# Puncher.net
KiCad netlist of a schematic drawn in EAGLE
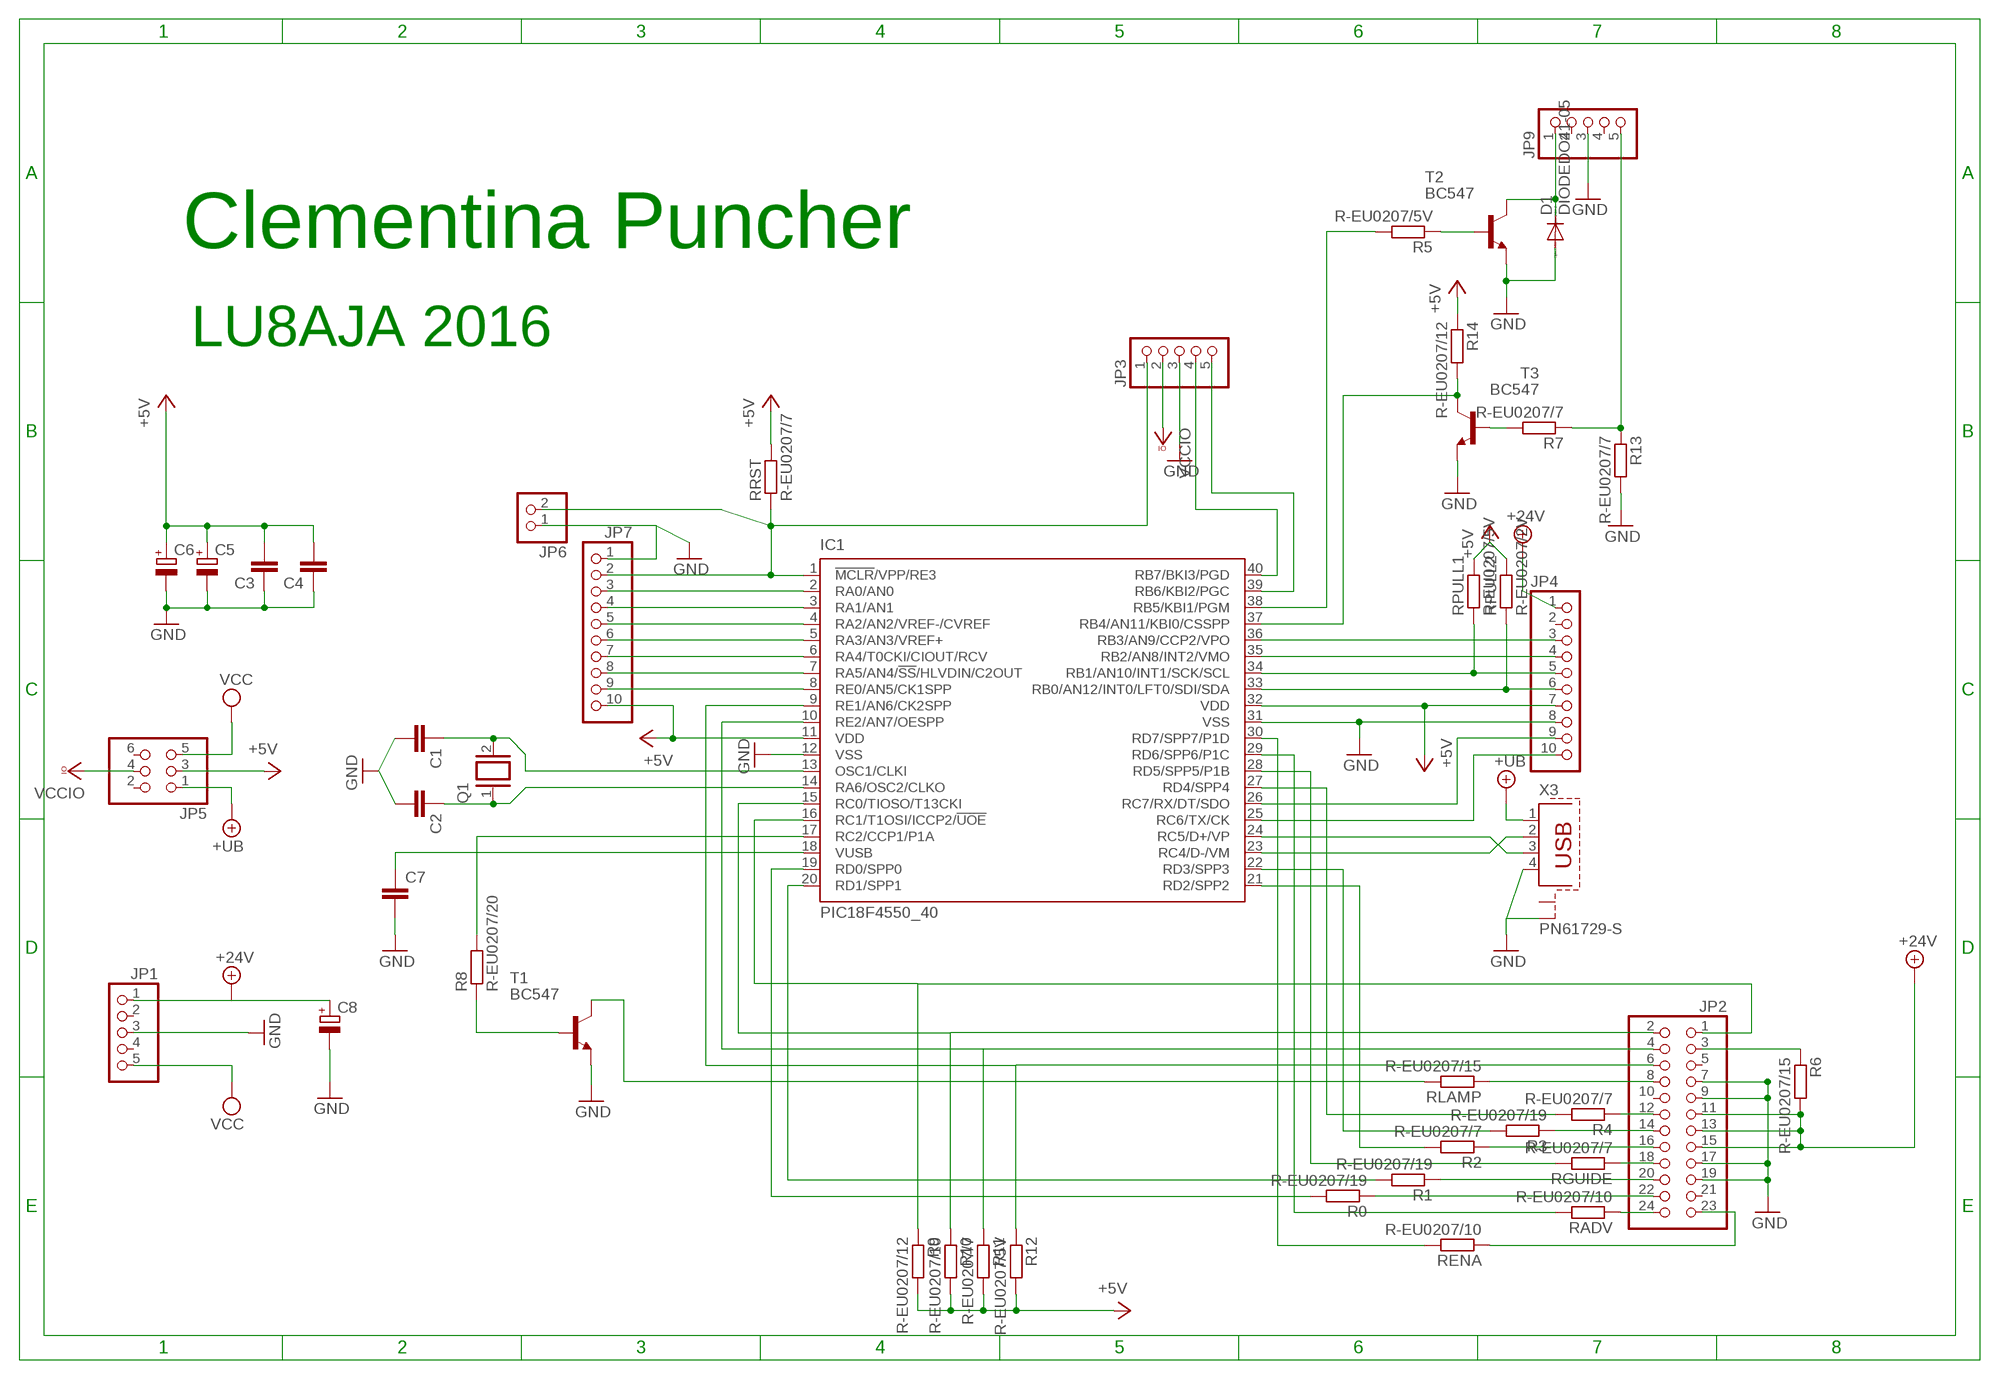
[diagram p0: schematic, sheet 1]

(export (version "E")
  (design (tool "Eeschema 10.0.6"))
  (components
    (comp (ref "C1")
      (value "C-EU025-025X050")
      (footprint "eagle-import:C025-025X050")
      (libsource (lib "eagle-import") (part "rcl_C-EU025-025X050"))
    )
    (comp (ref "C2")
      (value "C-EU025-025X050")
      (footprint "eagle-import:C025-025X050")
      (libsource (lib "eagle-import") (part "rcl_C-EU025-025X050"))
    )
    (comp (ref "C3")
      (value "C-EU050-025X075")
      (footprint "eagle-import:C050-025X075")
      (libsource (lib "eagle-import") (part "rcl_C-EU050-025X075"))
    )
    (comp (ref "C4")
      (value "C-EU025-030X050")
      (footprint "eagle-import:C025-030X050")
      (libsource (lib "eagle-import") (part "C-EU025-030X050"))
    )
    (comp (ref "C5")
      (value "CPOL-EUE5-8.5")
      (footprint "eagle-import:E5-8,5")
      (libsource (lib "eagle-import") (part "rcl_CPOL-EUE5-8.5"))
    )
    (comp (ref "C6")
      (value "CPOL-EUE5-8.5")
      (footprint "eagle-import:E5-8,5")
      (libsource (lib "eagle-import") (part "rcl_CPOL-EUE5-8.5"))
    )
    (comp (ref "C7")
      (value "C-EU050-025X075")
      (footprint "eagle-import:C050-025X075")
      (libsource (lib "eagle-import") (part "C-EU050-025X075"))
    )
    (comp (ref "C8")
      (value "CPOL-EUE5-8.5")
      (footprint "eagle-import:E5-8,5")
      (libsource (lib "eagle-import") (part "CPOL-EUE5-8.5"))
    )
    (comp (ref "D1")
      (value "DIODEDO41-05")
      (footprint "eagle-import:DO41-05")
      (libsource (lib "eagle-import") (part "DIODEDO41-05"))
    )
    (comp (ref "IC1")
      (value "PIC18F4550_40")
      (footprint "eagle-import:DIL40")
      (fields (field (name "MF") "MICROCHIP") (field (name "MPN") "PIC18F4550-I/P"))
      (libsource (lib "eagle-import") (part "PIC18F4_40550"))
    )
    (comp (ref "JP1")
      (value "PINHD-1X5")
      (footprint "eagle-import:1X05")
      (libsource (lib "eagle-import") (part "PINHD-1X5"))
    )
    (comp (ref "JP2")
      (value "PINHD-2X12")
      (footprint "eagle-import:2X12")
      (libsource (lib "eagle-import") (part "PINHD-2X12"))
    )
    (comp (ref "JP3")
      (value "PINHD-1X5")
      (footprint "eagle-import:1X05")
      (libsource (lib "eagle-import") (part "PINHD-1X5"))
    )
    (comp (ref "JP4")
      (value "PINHD-1X10")
      (footprint "eagle-import:1X10")
      (libsource (lib "eagle-import") (part "PINHD-1X10"))
    )
    (comp (ref "JP5")
      (value "PINHD-2X3")
      (footprint "eagle-import:2X03")
      (libsource (lib "eagle-import") (part "PINHD-2X3"))
    )
    (comp (ref "JP6")
      (value "PINHD-1X2")
      (footprint "eagle-import:1X02")
      (libsource (lib "eagle-import") (part "PINHD-1X2"))
    )
    (comp (ref "JP7")
      (value "PINHD-1X10")
      (footprint "eagle-import:1X10")
      (libsource (lib "eagle-import") (part "PINHD-1X10"))
    )
    (comp (ref "JP9")
      (value "PINHD-1X5")
      (footprint "eagle-import:1X05")
      (libsource (lib "eagle-import") (part "PINHD-1X5"))
    )
    (comp (ref "Q1")
      (value "XTAL/S")
      (footprint "eagle-import:QS")
      (libsource (lib "eagle-import") (part "XTAL/S"))
    )
    (comp (ref "R0")
      (value "R-EU0207/19")
      (footprint "eagle-import:0207_19")
      (libsource (lib "eagle-import") (part "R-EU0207/19"))
    )
    (comp (ref "R1")
      (value "R-EU0207/19")
      (footprint "eagle-import:0207_19")
      (libsource (lib "eagle-import") (part "R-EU0207/19"))
    )
    (comp (ref "R2")
      (value "R-EU0207/7")
      (footprint "eagle-import:0207_7")
      (libsource (lib "eagle-import") (part "R-EU0207/7"))
    )
    (comp (ref "R3")
      (value "R-EU0207/19")
      (footprint "eagle-import:0207_19")
      (libsource (lib "eagle-import") (part "R-EU0207/19"))
    )
    (comp (ref "R4")
      (value "R-EU0207/7")
      (footprint "eagle-import:0207_7")
      (libsource (lib "eagle-import") (part "R-EU0207/7"))
    )
    (comp (ref "R5")
      (value "R-EU0207/5V")
      (footprint "eagle-import:0207_5V")
      (libsource (lib "eagle-import") (part "R-EU0207/5V"))
    )
    (comp (ref "R6")
      (value "R-EU0207/15")
      (footprint "eagle-import:0207_15")
      (libsource (lib "eagle-import") (part "R-EU0207/15"))
    )
    (comp (ref "R7")
      (value "R-EU0207/7")
      (footprint "eagle-import:0207_7")
      (libsource (lib "eagle-import") (part "R-EU0207/7"))
    )
    (comp (ref "R8")
      (value "R-EU0207/20")
      (footprint "eagle-import:0207_20")
      (libsource (lib "eagle-import") (part "R-EU0207/20"))
    )
    (comp (ref "R9")
      (value "R-EU0207/12")
      (footprint "eagle-import:0207_12")
      (libsource (lib "eagle-import") (part "R-EU0207/12"))
    )
    (comp (ref "R10")
      (value "R-EU0207/10")
      (footprint "eagle-import:0207_10")
      (libsource (lib "eagle-import") (part "R-EU0207/10"))
    )
    (comp (ref "R11")
      (value "R-EU0207/7")
      (footprint "eagle-import:0207_7")
      (libsource (lib "eagle-import") (part "R-EU0207/7"))
    )
    (comp (ref "R12")
      (value "R-EU0207/5V")
      (footprint "eagle-import:0207_5V")
      (libsource (lib "eagle-import") (part "R-EU0207/5V"))
    )
    (comp (ref "R13")
      (value "R-EU0207/7")
      (footprint "eagle-import:0207_7")
      (libsource (lib "eagle-import") (part "R-EU0207/7"))
    )
    (comp (ref "R14")
      (value "R-EU0207/12")
      (footprint "eagle-import:0207_12")
      (libsource (lib "eagle-import") (part "R-EU0207/12"))
    )
    (comp (ref "RADV")
      (value "R-EU0207/10")
      (footprint "eagle-import:0207_10")
      (libsource (lib "eagle-import") (part "R-EU0207/10"))
    )
    (comp (ref "RENA")
      (value "R-EU0207/10")
      (footprint "eagle-import:0207_10")
      (libsource (lib "eagle-import") (part "R-EU0207/10"))
    )
    (comp (ref "RGUIDE")
      (value "R-EU0207/7")
      (footprint "eagle-import:0207_7")
      (libsource (lib "eagle-import") (part "R-EU0207/7"))
    )
    (comp (ref "RLAMP")
      (value "R-EU0207/15")
      (footprint "eagle-import:0207_15")
      (libsource (lib "eagle-import") (part "R-EU0207/15"))
    )
    (comp (ref "RPULL1")
      (value "R-EU0207/5V")
      (footprint "eagle-import:0207_5V")
      (libsource (lib "eagle-import") (part "R-EU0207/5V"))
    )
    (comp (ref "RPULL2")
      (value "R-EU0207/2V")
      (footprint "eagle-import:0207_2V")
      (libsource (lib "eagle-import") (part "R-EU0207/2V"))
    )
    (comp (ref "RRST")
      (value "R-EU0207/7")
      (footprint "eagle-import:0207_7")
      (libsource (lib "eagle-import") (part "R-EU0207/7"))
    )
    (comp (ref "T1")
      (value "BC547")
      (footprint "eagle-import:TO92")
      (libsource (lib "eagle-import") (part "BC547"))
    )
    (comp (ref "T2")
      (value "BC547")
      (footprint "eagle-import:TO92")
      (libsource (lib "eagle-import") (part "BC547"))
    )
    (comp (ref "T3")
      (value "BC547")
      (footprint "eagle-import:TO92")
      (libsource (lib "eagle-import") (part "BC547"))
    )
    (comp (ref "X3")
      (value "PN61729-S")
      (footprint "eagle-import:PN61729-S")
      (libsource (lib "eagle-import") (part "PN61729-S"))
    )
  )
  (nets
    (net (code "1") (name "+5V") (class "Default")
      (node (ref "C3") (pin "2") (pinfunction "2_2") (pintype "passive"))
      (node (ref "C4") (pin "2") (pinfunction "2_2") (pintype "passive"))
      (node (ref "C5") (pin "+") (pinfunction "+_+") (pintype "passive"))
      (node (ref "C6") (pin "+") (pinfunction "+_+") (pintype "passive"))
      (node (ref "IC1") (pin "11") (pinfunction "VDD_11") (pintype "power_in"))
      (node (ref "IC1") (pin "32") (pinfunction "VDD_32") (pintype "power_in"))
      (node (ref "JP4") (pin "7") (pinfunction "7_7") (pintype "passive"))
      (node (ref "JP5") (pin "3") (pinfunction "3_3") (pintype "passive"))
      (node (ref "JP7") (pin "10") (pinfunction "10_10") (pintype "passive"))
      (node (ref "R10") (pin "2") (pinfunction "2_2") (pintype "passive"))
      (node (ref "R11") (pin "2") (pinfunction "2_2") (pintype "passive"))
      (node (ref "R12") (pin "2") (pinfunction "2_2") (pintype "passive"))
      (node (ref "R14") (pin "1") (pinfunction "1_1") (pintype "passive"))
      (node (ref "R9") (pin "2") (pinfunction "2_2") (pintype "passive"))
      (node (ref "RPULL1") (pin "2") (pinfunction "2_2") (pintype "passive"))
      (node (ref "RPULL2") (pin "2") (pinfunction "2_2") (pintype "passive"))
      (node (ref "RRST") (pin "2") (pinfunction "2_2") (pintype "passive"))
    )
    (net (code "2") (name "+24V") (class "Default")
      (node (ref "C8") (pin "+") (pinfunction "+_+") (pintype "passive"))
      (node (ref "JP1") (pin "1") (pinfunction "1_1") (pintype "passive"))
      (node (ref "JP2") (pin "11") (pinfunction "11_11") (pintype "passive"))
      (node (ref "JP2") (pin "13") (pinfunction "13_13") (pintype "passive"))
      (node (ref "JP2") (pin "15") (pinfunction "15_15") (pintype "passive"))
      (node (ref "JP4") (pin "1") (pinfunction "1_1") (pintype "passive"))
      (node (ref "R6") (pin "2") (pinfunction "2_2") (pintype "passive"))
    )
    (net (code "3") (name "+UB") (class "Default")
      (node (ref "JP5") (pin "1") (pinfunction "1_1") (pintype "passive"))
      (node (ref "X3") (pin "1") (pinfunction "1_1") (pintype "passive"))
    )
    (net (code "4") (name "GND") (class "Default")
      (node (ref "C1") (pin "2") (pinfunction "2_2") (pintype "passive"))
      (node (ref "C2") (pin "2") (pinfunction "2_2") (pintype "passive"))
      (node (ref "C3") (pin "1") (pinfunction "1_1") (pintype "passive"))
      (node (ref "C4") (pin "1") (pinfunction "1_1") (pintype "passive"))
      (node (ref "C5") (pin "-") (pinfunction "-_-") (pintype "passive"))
      (node (ref "C6") (pin "-") (pinfunction "-_-") (pintype "passive"))
      (node (ref "C7") (pin "2") (pinfunction "2_2") (pintype "passive"))
      (node (ref "C8") (pin "-") (pinfunction "-_-") (pintype "passive"))
      (node (ref "D1") (pin "A") (pinfunction "A_A") (pintype "passive"))
      (node (ref "IC1") (pin "12") (pinfunction "VSS_12") (pintype "power_in"))
      (node (ref "IC1") (pin "31") (pinfunction "VSS_31") (pintype "power_in"))
      (node (ref "JP1") (pin "3") (pinfunction "3_3") (pintype "passive"))
      (node (ref "JP2") (pin "17") (pinfunction "17_17") (pintype "passive"))
      (node (ref "JP2") (pin "19") (pinfunction "19_19") (pintype "passive"))
      (node (ref "JP2") (pin "7") (pinfunction "7_7") (pintype "passive"))
      (node (ref "JP2") (pin "9") (pinfunction "9_9") (pintype "passive"))
      (node (ref "JP3") (pin "3") (pinfunction "3_3") (pintype "passive"))
      (node (ref "JP4") (pin "8") (pinfunction "8_8") (pintype "passive"))
      (node (ref "JP6") (pin "1") (pinfunction "1_1") (pintype "passive"))
      (node (ref "JP7") (pin "1") (pinfunction "1_1") (pintype "passive"))
      (node (ref "JP9") (pin "3") (pinfunction "3_3") (pintype "passive"))
      (node (ref "R13") (pin "2") (pinfunction "2_2") (pintype "passive"))
      (node (ref "T1") (pin "1") (pinfunction "E_1") (pintype "passive"))
      (node (ref "T2") (pin "1") (pinfunction "E_1") (pintype "passive"))
      (node (ref "T3") (pin "1") (pinfunction "E_1") (pintype "passive"))
      (node (ref "X3") (pin "4") (pinfunction "4_4") (pintype "passive"))
      (node (ref "X3") (pin "S2") (pinfunction "S2_S2") (pintype "passive"))
    )
    (net (code "5") (name "Net-(IC1-OSC1{slash}CLKI)") (class "Default")
      (node (ref "C1") (pin "1") (pinfunction "1_1") (pintype "passive"))
      (node (ref "IC1") (pin "13") (pinfunction "OSC1/CLKI_13") (pintype "input"))
      (node (ref "Q1") (pin "2") (pinfunction "2_2") (pintype "passive"))
    )
    (net (code "6") (name "Net-(IC1-RA0{slash}AN0)") (class "Default")
      (node (ref "IC1") (pin "2") (pinfunction "RA0/AN0_2") (pintype "bidirectional"))
      (node (ref "JP7") (pin "3") (pinfunction "3_3") (pintype "passive"))
    )
    (net (code "7") (name "Net-(IC1-RA1{slash}AN1)") (class "Default")
      (node (ref "IC1") (pin "3") (pinfunction "RA1/AN1_3") (pintype "bidirectional"))
      (node (ref "JP7") (pin "4") (pinfunction "4_4") (pintype "passive"))
    )
    (net (code "8") (name "Net-(IC1-RA2{slash}AN2{slash}VREF-{slash}CVREF)") (class "Default")
      (node (ref "IC1") (pin "4") (pinfunction "RA2/AN2/VREF-/CVREF_4") (pintype "bidirectional"))
      (node (ref "JP7") (pin "5") (pinfunction "5_5") (pintype "passive"))
    )
    (net (code "9") (name "Net-(IC1-RA3{slash}AN3{slash}VREF+)") (class "Default")
      (node (ref "IC1") (pin "5") (pinfunction "RA3/AN3/VREF+_5") (pintype "bidirectional"))
      (node (ref "JP7") (pin "6") (pinfunction "6_6") (pintype "passive"))
    )
    (net (code "10") (name "Net-(IC1-RA4{slash}T0CKI{slash}CIOUT{slash}RCV)") (class "Default")
      (node (ref "IC1") (pin "6") (pinfunction "RA4/T0CKI/CIOUT/RCV_6") (pintype "bidirectional"))
      (node (ref "JP7") (pin "7") (pinfunction "7_7") (pintype "passive"))
    )
    (net (code "11") (name "Net-(IC1-RA5{slash}AN4{slash}~{SS}{slash}HLVDIN{slash}C2OUT)") (class "Default")
      (node (ref "IC1") (pin "7") (pinfunction "RA5/AN4/~{SS}/HLVDIN/C2OUT_7") (pintype "bidirectional"))
      (node (ref "JP7") (pin "8") (pinfunction "8_8") (pintype "passive"))
    )
    (net (code "12") (name "Net-(IC1-RA6{slash}OSC2{slash}CLKO)") (class "Default")
      (node (ref "C2") (pin "1") (pinfunction "1_1") (pintype "passive"))
      (node (ref "IC1") (pin "14") (pinfunction "RA6/OSC2/CLKO_14") (pintype "output"))
      (node (ref "Q1") (pin "1") (pinfunction "1_1") (pintype "passive"))
    )
    (net (code "13") (name "Net-(IC1-RB0{slash}AN12{slash}INT0{slash}LFT0{slash}SDI{slash}SDA)") (class "Default")
      (node (ref "IC1") (pin "33") (pinfunction "RB0/AN12/INT0/LFT0/SDI/SDA_33") (pintype "bidirectional"))
      (node (ref "JP4") (pin "6") (pinfunction "6_6") (pintype "passive"))
      (node (ref "RPULL2") (pin "1") (pinfunction "1_1") (pintype "passive"))
    )
    (net (code "14") (name "Net-(IC1-RB1{slash}AN10{slash}INT1{slash}SCK{slash}SCL)") (class "Default")
      (node (ref "IC1") (pin "34") (pinfunction "RB1/AN10/INT1/SCK/SCL_34") (pintype "bidirectional"))
      (node (ref "JP4") (pin "5") (pinfunction "5_5") (pintype "passive"))
      (node (ref "RPULL1") (pin "1") (pinfunction "1_1") (pintype "passive"))
    )
    (net (code "15") (name "Net-(IC1-RB2{slash}AN8{slash}INT2{slash}VMO)") (class "Default")
      (node (ref "IC1") (pin "35") (pinfunction "RB2/AN8/INT2/VMO_35") (pintype "bidirectional"))
      (node (ref "JP4") (pin "4") (pinfunction "4_4") (pintype "passive"))
    )
    (net (code "16") (name "Net-(IC1-RB3{slash}AN9{slash}CCP2{slash}VPO)") (class "Default")
      (node (ref "IC1") (pin "36") (pinfunction "RB3/AN9/CCP2/VPO_36") (pintype "bidirectional"))
      (node (ref "JP4") (pin "3") (pinfunction "3_3") (pintype "passive"))
    )
    (net (code "17") (name "Net-(IC1-RB4{slash}AN11{slash}KBI0{slash}CSSPP)") (class "Default")
      (node (ref "IC1") (pin "37") (pinfunction "RB4/AN11/KBI0/CSSPP_37") (pintype "bidirectional"))
      (node (ref "R14") (pin "2") (pinfunction "2_2") (pintype "passive"))
      (node (ref "T3") (pin "3") (pinfunction "C_3") (pintype "passive"))
    )
    (net (code "18") (name "Net-(IC1-RB5{slash}KBI1{slash}PGM)") (class "Default")
      (node (ref "IC1") (pin "38") (pinfunction "RB5/KBI1/PGM_38") (pintype "bidirectional"))
      (node (ref "R5") (pin "2") (pinfunction "2_2") (pintype "passive"))
    )
    (net (code "19") (name "Net-(IC1-RB6{slash}KBI2{slash}PGC)") (class "Default")
      (node (ref "IC1") (pin "39") (pinfunction "RB6/KBI2/PGC_39") (pintype "bidirectional"))
      (node (ref "JP3") (pin "5") (pinfunction "5_5") (pintype "passive"))
    )
    (net (code "20") (name "Net-(IC1-RB7{slash}BKI3{slash}PGD)") (class "Default")
      (node (ref "IC1") (pin "40") (pinfunction "RB7/BKI3/PGD_40") (pintype "bidirectional"))
      (node (ref "JP3") (pin "4") (pinfunction "4_4") (pintype "passive"))
    )
    (net (code "21") (name "Net-(IC1-RC0{slash}TIOSO{slash}T13CKI)") (class "Default")
      (node (ref "IC1") (pin "15") (pinfunction "RC0/TIOSO/T13CKI_15") (pintype "bidirectional"))
      (node (ref "JP2") (pin "2") (pinfunction "2_2") (pintype "passive"))
      (node (ref "R10") (pin "1") (pinfunction "1_1") (pintype "passive"))
    )
    (net (code "22") (name "Net-(IC1-RC1{slash}T1OSI{slash}ICCP2{slash}~{UOE})") (class "Default")
      (node (ref "IC1") (pin "16") (pinfunction "RC1/T1OSI/ICCP2/~{UOE}_16") (pintype "bidirectional"))
      (node (ref "JP2") (pin "1") (pinfunction "1_1") (pintype "passive"))
      (node (ref "R9") (pin "1") (pinfunction "1_1") (pintype "passive"))
    )
    (net (code "23") (name "Net-(IC1-RC2{slash}CCP1{slash}P1A)") (class "Default")
      (node (ref "IC1") (pin "17") (pinfunction "RC2/CCP1/P1A_17") (pintype "bidirectional"))
      (node (ref "R8") (pin "2") (pinfunction "2_2") (pintype "passive"))
    )
    (net (code "24") (name "Net-(IC1-RC4{slash}D-{slash}VM)") (class "Default")
      (node (ref "IC1") (pin "23") (pinfunction "RC4/D-/VM_23") (pintype "bidirectional"))
      (node (ref "X3") (pin "2") (pinfunction "2_2") (pintype "passive"))
    )
    (net (code "25") (name "Net-(IC1-RC5{slash}D+{slash}VP)") (class "Default")
      (node (ref "IC1") (pin "24") (pinfunction "RC5/D+/VP_24") (pintype "bidirectional"))
      (node (ref "X3") (pin "3") (pinfunction "3_3") (pintype "passive"))
    )
    (net (code "26") (name "Net-(IC1-RC6{slash}TX{slash}CK)") (class "Default")
      (node (ref "IC1") (pin "25") (pinfunction "RC6/TX/CK_25") (pintype "bidirectional"))
      (node (ref "JP4") (pin "10") (pinfunction "10_10") (pintype "passive"))
    )
    (net (code "27") (name "Net-(IC1-RC7{slash}RX{slash}DT{slash}SDO)") (class "Default")
      (node (ref "IC1") (pin "26") (pinfunction "RC7/RX/DT/SDO_26") (pintype "bidirectional"))
      (node (ref "JP4") (pin "9") (pinfunction "9_9") (pintype "passive"))
    )
    (net (code "28") (name "Net-(IC1-RD0{slash}SPP0)") (class "Default")
      (node (ref "IC1") (pin "19") (pinfunction "RD0/SPP0_19") (pintype "bidirectional"))
      (node (ref "R0") (pin "2") (pinfunction "2_2") (pintype "passive"))
    )
    (net (code "29") (name "Net-(IC1-RD1{slash}SPP1)") (class "Default")
      (node (ref "IC1") (pin "20") (pinfunction "RD1/SPP1_20") (pintype "bidirectional"))
      (node (ref "R1") (pin "2") (pinfunction "2_2") (pintype "passive"))
    )
    (net (code "30") (name "Net-(IC1-RD2{slash}SPP2)") (class "Default")
      (node (ref "IC1") (pin "21") (pinfunction "RD2/SPP2_21") (pintype "bidirectional"))
      (node (ref "R2") (pin "2") (pinfunction "2_2") (pintype "passive"))
    )
    (net (code "31") (name "Net-(IC1-RD3{slash}SPP3)") (class "Default")
      (node (ref "IC1") (pin "22") (pinfunction "RD3/SPP3_22") (pintype "bidirectional"))
      (node (ref "R3") (pin "2") (pinfunction "2_2") (pintype "passive"))
    )
    (net (code "32") (name "Net-(IC1-RD4{slash}SPP4)") (class "Default")
      (node (ref "IC1") (pin "27") (pinfunction "RD4/SPP4_27") (pintype "bidirectional"))
      (node (ref "R4") (pin "2") (pinfunction "2_2") (pintype "passive"))
    )
    (net (code "33") (name "Net-(IC1-RD5{slash}SPP5{slash}P1B)") (class "Default")
      (node (ref "IC1") (pin "28") (pinfunction "RD5/SPP5/P1B_28") (pintype "bidirectional"))
      (node (ref "RGUIDE") (pin "2") (pinfunction "2_2") (pintype "passive"))
    )
    (net (code "34") (name "Net-(IC1-RD6{slash}SPP6{slash}P1C)") (class "Default")
      (node (ref "IC1") (pin "29") (pinfunction "RD6/SPP6/P1C_29") (pintype "bidirectional"))
      (node (ref "RADV") (pin "2") (pinfunction "2_2") (pintype "passive"))
    )
    (net (code "35") (name "Net-(IC1-RD7{slash}SPP7{slash}P1D)") (class "Default")
      (node (ref "IC1") (pin "30") (pinfunction "RD7/SPP7/P1D_30") (pintype "bidirectional"))
      (node (ref "RENA") (pin "2") (pinfunction "2_2") (pintype "passive"))
    )
    (net (code "36") (name "Net-(IC1-RE0{slash}AN5{slash}CK1SPP)") (class "Default")
      (node (ref "IC1") (pin "8") (pinfunction "RE0/AN5/CK1SPP_8") (pintype "bidirectional"))
      (node (ref "JP7") (pin "9") (pinfunction "9_9") (pintype "passive"))
    )
    (net (code "37") (name "Net-(IC1-RE1{slash}AN6{slash}CK2SPP)") (class "Default")
      (node (ref "IC1") (pin "9") (pinfunction "RE1/AN6/CK2SPP_9") (pintype "bidirectional"))
      (node (ref "JP2") (pin "6") (pinfunction "6_6") (pintype "passive"))
      (node (ref "R12") (pin "1") (pinfunction "1_1") (pintype "passive"))
    )
    (net (code "38") (name "Net-(IC1-RE2{slash}AN7{slash}OESPP)") (class "Default")
      (node (ref "IC1") (pin "10") (pinfunction "RE2/AN7/OESPP_10") (pintype "bidirectional"))
      (node (ref "JP2") (pin "4") (pinfunction "4_4") (pintype "passive"))
      (node (ref "R11") (pin "1") (pinfunction "1_1") (pintype "passive"))
    )
    (net (code "39") (name "Net-(IC1-VUSB)") (class "Default")
      (node (ref "C7") (pin "1") (pinfunction "1_1") (pintype "passive"))
      (node (ref "IC1") (pin "18") (pinfunction "VUSB_18") (pintype "bidirectional"))
    )
    (net (code "40") (name "Net-(IC1-~{MCLR}{slash}VPP{slash}RE3)") (class "Default")
      (node (ref "IC1") (pin "1") (pinfunction "~{MCLR}/VPP/RE3_1") (pintype "input"))
      (node (ref "JP3") (pin "1") (pinfunction "1_1") (pintype "passive"))
      (node (ref "JP6") (pin "2") (pinfunction "2_2") (pintype "passive"))
      (node (ref "JP7") (pin "2") (pinfunction "2_2") (pintype "passive"))
      (node (ref "RRST") (pin "1") (pinfunction "1_1") (pintype "passive"))
    )
    (net (code "41") (name "Net-(JP2-Pad3)") (class "Default")
      (node (ref "JP2") (pin "3") (pinfunction "3_3") (pintype "passive"))
      (node (ref "R6") (pin "1") (pinfunction "1_1") (pintype "passive"))
    )
    (net (code "42") (name "Net-(JP2-Pad8)") (class "Default")
      (node (ref "JP2") (pin "8") (pinfunction "8_8") (pintype "passive"))
      (node (ref "RLAMP") (pin "1") (pinfunction "1_1") (pintype "passive"))
    )
    (net (code "43") (name "Net-(JP2-Pad12)") (class "Default")
      (node (ref "JP2") (pin "12") (pinfunction "12_12") (pintype "passive"))
      (node (ref "R4") (pin "1") (pinfunction "1_1") (pintype "passive"))
    )
    (net (code "44") (name "Net-(JP2-Pad14)") (class "Default")
      (node (ref "JP2") (pin "14") (pinfunction "14_14") (pintype "passive"))
      (node (ref "R3") (pin "1") (pinfunction "1_1") (pintype "passive"))
    )
    (net (code "45") (name "Net-(JP2-Pad16)") (class "Default")
      (node (ref "JP2") (pin "16") (pinfunction "16_16") (pintype "passive"))
      (node (ref "R2") (pin "1") (pinfunction "1_1") (pintype "passive"))
    )
    (net (code "46") (name "Net-(JP2-Pad18)") (class "Default")
      (node (ref "JP2") (pin "18") (pinfunction "18_18") (pintype "passive"))
      (node (ref "RGUIDE") (pin "1") (pinfunction "1_1") (pintype "passive"))
    )
    (net (code "47") (name "Net-(JP2-Pad20)") (class "Default")
      (node (ref "JP2") (pin "20") (pinfunction "20_20") (pintype "passive"))
      (node (ref "R1") (pin "1") (pinfunction "1_1") (pintype "passive"))
    )
    (net (code "48") (name "Net-(JP2-Pad22)") (class "Default")
      (node (ref "JP2") (pin "22") (pinfunction "22_22") (pintype "passive"))
      (node (ref "R0") (pin "1") (pinfunction "1_1") (pintype "passive"))
    )
    (net (code "49") (name "Net-(JP2-Pad23)") (class "Default")
      (node (ref "JP2") (pin "23") (pinfunction "23_23") (pintype "passive"))
      (node (ref "RENA") (pin "1") (pinfunction "1_1") (pintype "passive"))
    )
    (net (code "50") (name "Net-(JP2-Pad24)") (class "Default")
      (node (ref "JP2") (pin "24") (pinfunction "24_24") (pintype "passive"))
      (node (ref "RADV") (pin "1") (pinfunction "1_1") (pintype "passive"))
    )
    (net (code "51") (name "Net-(JP9-Pad5)") (class "Default")
      (node (ref "JP9") (pin "5") (pinfunction "5_5") (pintype "passive"))
      (node (ref "R13") (pin "1") (pinfunction "1_1") (pintype "passive"))
      (node (ref "R7") (pin "1") (pinfunction "1_1") (pintype "passive"))
    )
    (net (code "52") (name "Net-(T1-B)") (class "Default")
      (node (ref "R8") (pin "1") (pinfunction "1_1") (pintype "passive"))
      (node (ref "T1") (pin "2") (pinfunction "B_2") (pintype "passive"))
    )
    (net (code "53") (name "Net-(T1-C)") (class "Default")
      (node (ref "RLAMP") (pin "2") (pinfunction "2_2") (pintype "passive"))
      (node (ref "T1") (pin "3") (pinfunction "C_3") (pintype "passive"))
    )
    (net (code "54") (name "Net-(T2-B)") (class "Default")
      (node (ref "R5") (pin "1") (pinfunction "1_1") (pintype "passive"))
      (node (ref "T2") (pin "2") (pinfunction "B_2") (pintype "passive"))
    )
    (net (code "55") (name "Net-(T2-C)") (class "Default")
      (node (ref "D1") (pin "C") (pinfunction "C_C") (pintype "passive"))
      (node (ref "JP9") (pin "1") (pinfunction "1_1") (pintype "passive"))
      (node (ref "T2") (pin "3") (pinfunction "C_3") (pintype "passive"))
    )
    (net (code "56") (name "Net-(T3-B)") (class "Default")
      (node (ref "R7") (pin "2") (pinfunction "2_2") (pintype "passive"))
      (node (ref "T3") (pin "2") (pinfunction "B_2") (pintype "passive"))
    )
    (net (code "57") (name "VCC") (class "Default")
      (node (ref "JP1") (pin "5") (pinfunction "5_5") (pintype "passive"))
      (node (ref "JP5") (pin "5") (pinfunction "5_5") (pintype "passive"))
    )
    (net (code "58") (name "VCCIO") (class "Default")
      (node (ref "JP3") (pin "2") (pinfunction "2_2") (pintype "passive"))
      (node (ref "JP5") (pin "4") (pinfunction "4_4") (pintype "passive"))
    )
    (net (code "59") (name "unconnected-(JP1-Pad2)") (class "Default")
      (node (ref "JP1") (pin "2") (pinfunction "2_2") (pintype "passive"))
    )
    (net (code "60") (name "unconnected-(JP1-Pad4)") (class "Default")
      (node (ref "JP1") (pin "4") (pinfunction "4_4") (pintype "passive"))
    )
    (net (code "61") (name "unconnected-(JP2-Pad5)") (class "Default")
      (node (ref "JP2") (pin "5") (pinfunction "5_5") (pintype "passive"))
    )
    (net (code "62") (name "unconnected-(JP2-Pad10)") (class "Default")
      (node (ref "JP2") (pin "10") (pinfunction "10_10") (pintype "passive"))
    )
    (net (code "63") (name "unconnected-(JP2-Pad21)") (class "Default")
      (node (ref "JP2") (pin "21") (pinfunction "21_21") (pintype "passive"))
    )
    (net (code "64") (name "unconnected-(JP4-Pad2)") (class "Default")
      (node (ref "JP4") (pin "2") (pinfunction "2_2") (pintype "passive"))
    )
    (net (code "65") (name "unconnected-(JP5-Pad2)") (class "Default")
      (node (ref "JP5") (pin "2") (pinfunction "2_2") (pintype "passive"))
    )
    (net (code "66") (name "unconnected-(JP5-Pad6)") (class "Default")
      (node (ref "JP5") (pin "6") (pinfunction "6_6") (pintype "passive"))
    )
    (net (code "67") (name "unconnected-(JP9-Pad2)") (class "Default")
      (node (ref "JP9") (pin "2") (pinfunction "2_2") (pintype "passive"))
    )
    (net (code "68") (name "unconnected-(JP9-Pad4)") (class "Default")
      (node (ref "JP9") (pin "4") (pinfunction "4_4") (pintype "passive"))
    )
    (net (code "69") (name "unconnected-(X3-PadS1)") (class "Default")
      (node (ref "X3") (pin "S1") (pinfunction "S1_S1") (pintype "passive"))
    )
  )
)
